# PWR_SMPS_5A_36V.net
KiCad netlist of a schematic drawn in Altium Designer
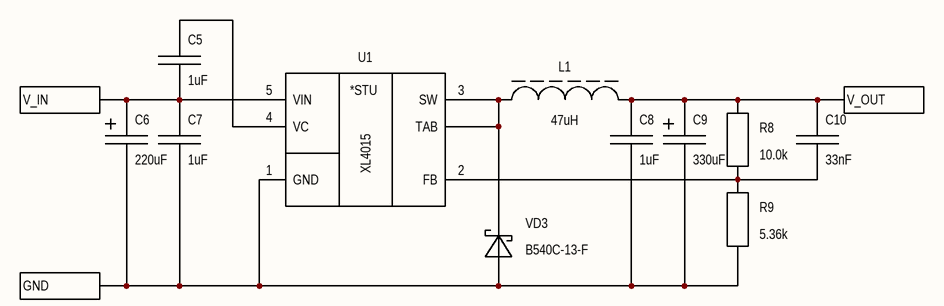
[diagram p0: PWR SMPS 5A 36V.SchDoc]

(export (version "E")
  (design (tool "Eeschema 10.0.6"))
  (components
    (comp (ref "C5")
      (value "1uF")
      (footprint "CAPC2012L")
      (description "Capacitor Ceramic 1uF 50V 0805(2012)")
      (fields (field (name "TOLERANCE") "±10%") (field (name "MANUFACTURER") "Yageo"))
      (libsource (lib "Capacitors") (part "CC0805KKX7R9BB105"))
    )
    (comp (ref "C6")
      (value "220uF")
      (footprint "CAPA10LS G")
      (description "Capacitor Aluminum 220uF 50V G")
      (fields (field (name "MANUFACTURER") "Nichicon") (field (name "VOLTAGE") "50"))
      (libsource (lib "Capacitors") (part "UCW1H221MNL1GS"))
    )
    (comp (ref "C7")
      (value "1uF")
      (footprint "CAPC2012L")
      (description "Capacitor Ceramic 1uF 50V 0805(2012)")
      (fields (field (name "TOLERANCE") "±10%") (field (name "MANUFACTURER") "Yageo"))
      (libsource (lib "Capacitors") (part "CC0805KKX7R9BB105"))
    )
    (comp (ref "C8")
      (value "1uF")
      (footprint "CAPC2012L")
      (description "Capacitor Ceramic 1uF 50V 0805(2012)")
      (fields (field (name "TOLERANCE") "±10%") (field (name "MANUFACTURER") "Yageo"))
      (libsource (lib "Capacitors") (part "CC0805KKX7R9BB105"))
    )
    (comp (ref "C9")
      (value "330uF")
      (footprint "CAPA8LS F")
      (description "Capacitor Aluminum 330uF 25V F")
      (fields (field (name "MANUFACTURER") "Nichicon") (field (name "VOLTAGE") "25"))
      (libsource (lib "Capacitors") (part "UWT1E331MNL1GS"))
    )
    (comp (ref "C10")
      (value "33nF")
      (footprint "CAPC1608L")
      (description "Capacitor Ceramic 33nF 50V 0603(1608)")
      (fields (field (name "TOLERANCE") "±10%") (field (name "MANUFACTURER") "Yageo"))
      (libsource (lib "Capacitors") (part "CC0603KRX7R9BB333"))
    )
    (comp (ref "L1")
      (value "47uH")
      (footprint "INDF13.5x12.5SSH")
      (description "Fixed Inductor 6.5A 47µH")
      (fields (field (name "TOLERANCE") "±20%") (field (name "MANUFACTURER") "Bourns"))
      (libsource (lib "Inductors") (part "SRP1265A-470M"))
    )
    (comp (ref "R8")
      (value "10.0k")
      (footprint "RESC1608L")
      (description "Resistor Ceramic 10k ±1% 0.1W 0603(1608)")
      (fields (field (name "MANUFACTURER") "Yageo") (field (name "TOLERANCE") "±1%"))
      (libsource (lib "Resistors") (part "RC0603FR-0710KL"))
    )
    (comp (ref "R9")
      (value "5.36k")
      (footprint "RESC1608L")
      (description "Resistor Ceramic 5.36k ±1% 0.1W 0603(1608)")
      (fields (field (name "MANUFACTURER") "Yageo") (field (name "TOLERANCE") "±1%"))
      (libsource (lib "Resistors") (part "RC0603FR-075K36L"))
    )
    (comp (ref "U1")
      (value "XL4015")
      (footprint "TO-263-5")
      (description "SWR Down 5A ADJ (8-36V)")
      (fields (field (name "MANUFACTURER") "XLSEMI"))
      (libsource (lib "Power") (part "XL4015"))
    )
    (comp (ref "VD3")
      (value "B540C-13-F")
      (footprint "DO-214AB")
      (description "Diode Schottky 5A 40V")
      (fields (field (name "MANUFACTURER") "Diodes Incorporated"))
      (libsource (lib "Discrete components") (part "B540C-13-F"))
    )
  )
  (nets
    (net (code "1") (name "/GND") (class "Default")
      (node (ref "C6") (pin "2") (pinfunction "2_2") (pintype "passive"))
      (node (ref "C7") (pin "2") (pinfunction "2_2") (pintype "passive"))
      (node (ref "C8") (pin "2") (pinfunction "2_2") (pintype "passive"))
      (node (ref "C9") (pin "2") (pinfunction "2_2") (pintype "passive"))
      (node (ref "R9") (pin "2") (pinfunction "2_2") (pintype "passive"))
      (node (ref "U1") (pin "1") (pinfunction "GND_1") (pintype "power_in"))
      (node (ref "VD3") (pin "1") (pinfunction "Anode_1") (pintype "passive"))
    )
    (net (code "2") (name "/V_IN") (class "Default")
      (node (ref "C5") (pin "2") (pinfunction "2_2") (pintype "passive"))
      (node (ref "C6") (pin "1") (pinfunction "1_1") (pintype "passive"))
      (node (ref "C7") (pin "1") (pinfunction "1_1") (pintype "passive"))
      (node (ref "U1") (pin "5") (pinfunction "VIN_5") (pintype "power_in"))
    )
    (net (code "3") (name "/V_OUT") (class "Default")
      (node (ref "C10") (pin "1") (pinfunction "1_1") (pintype "passive"))
      (node (ref "C8") (pin "1") (pinfunction "1_1") (pintype "passive"))
      (node (ref "C9") (pin "1") (pinfunction "1_1") (pintype "passive"))
      (node (ref "L1") (pin "2") (pinfunction "2_2") (pintype "passive"))
      (node (ref "R8") (pin "1") (pinfunction "1_1") (pintype "passive"))
    )
    (net (code "4") (name "Net-(U1-FB)") (class "Default")
      (node (ref "C10") (pin "2") (pinfunction "2_2") (pintype "passive"))
      (node (ref "R8") (pin "2") (pinfunction "2_2") (pintype "passive"))
      (node (ref "R9") (pin "1") (pinfunction "1_1") (pintype "passive"))
      (node (ref "U1") (pin "2") (pinfunction "FB_2") (pintype "passive"))
    )
    (net (code "5") (name "Net-(U1-SW)") (class "Default")
      (node (ref "L1") (pin "1") (pinfunction "1_1") (pintype "passive"))
      (node (ref "U1") (pin "3") (pinfunction "SW_3") (pintype "power_in"))
      (node (ref "U1") (pin "6") (pinfunction "TAB_6") (pintype "power_in"))
      (node (ref "VD3") (pin "2") (pinfunction "Cathode_2") (pintype "passive"))
    )
    (net (code "6") (name "Net-(U1-VC)") (class "Default")
      (node (ref "C5") (pin "1") (pinfunction "1_1") (pintype "passive"))
      (node (ref "U1") (pin "4") (pinfunction "VC_4") (pintype "passive"))
    )
  )
)
